# frm-mw-diode-detector.net
KiCad netlist of a schematic drawn in Altium Designer
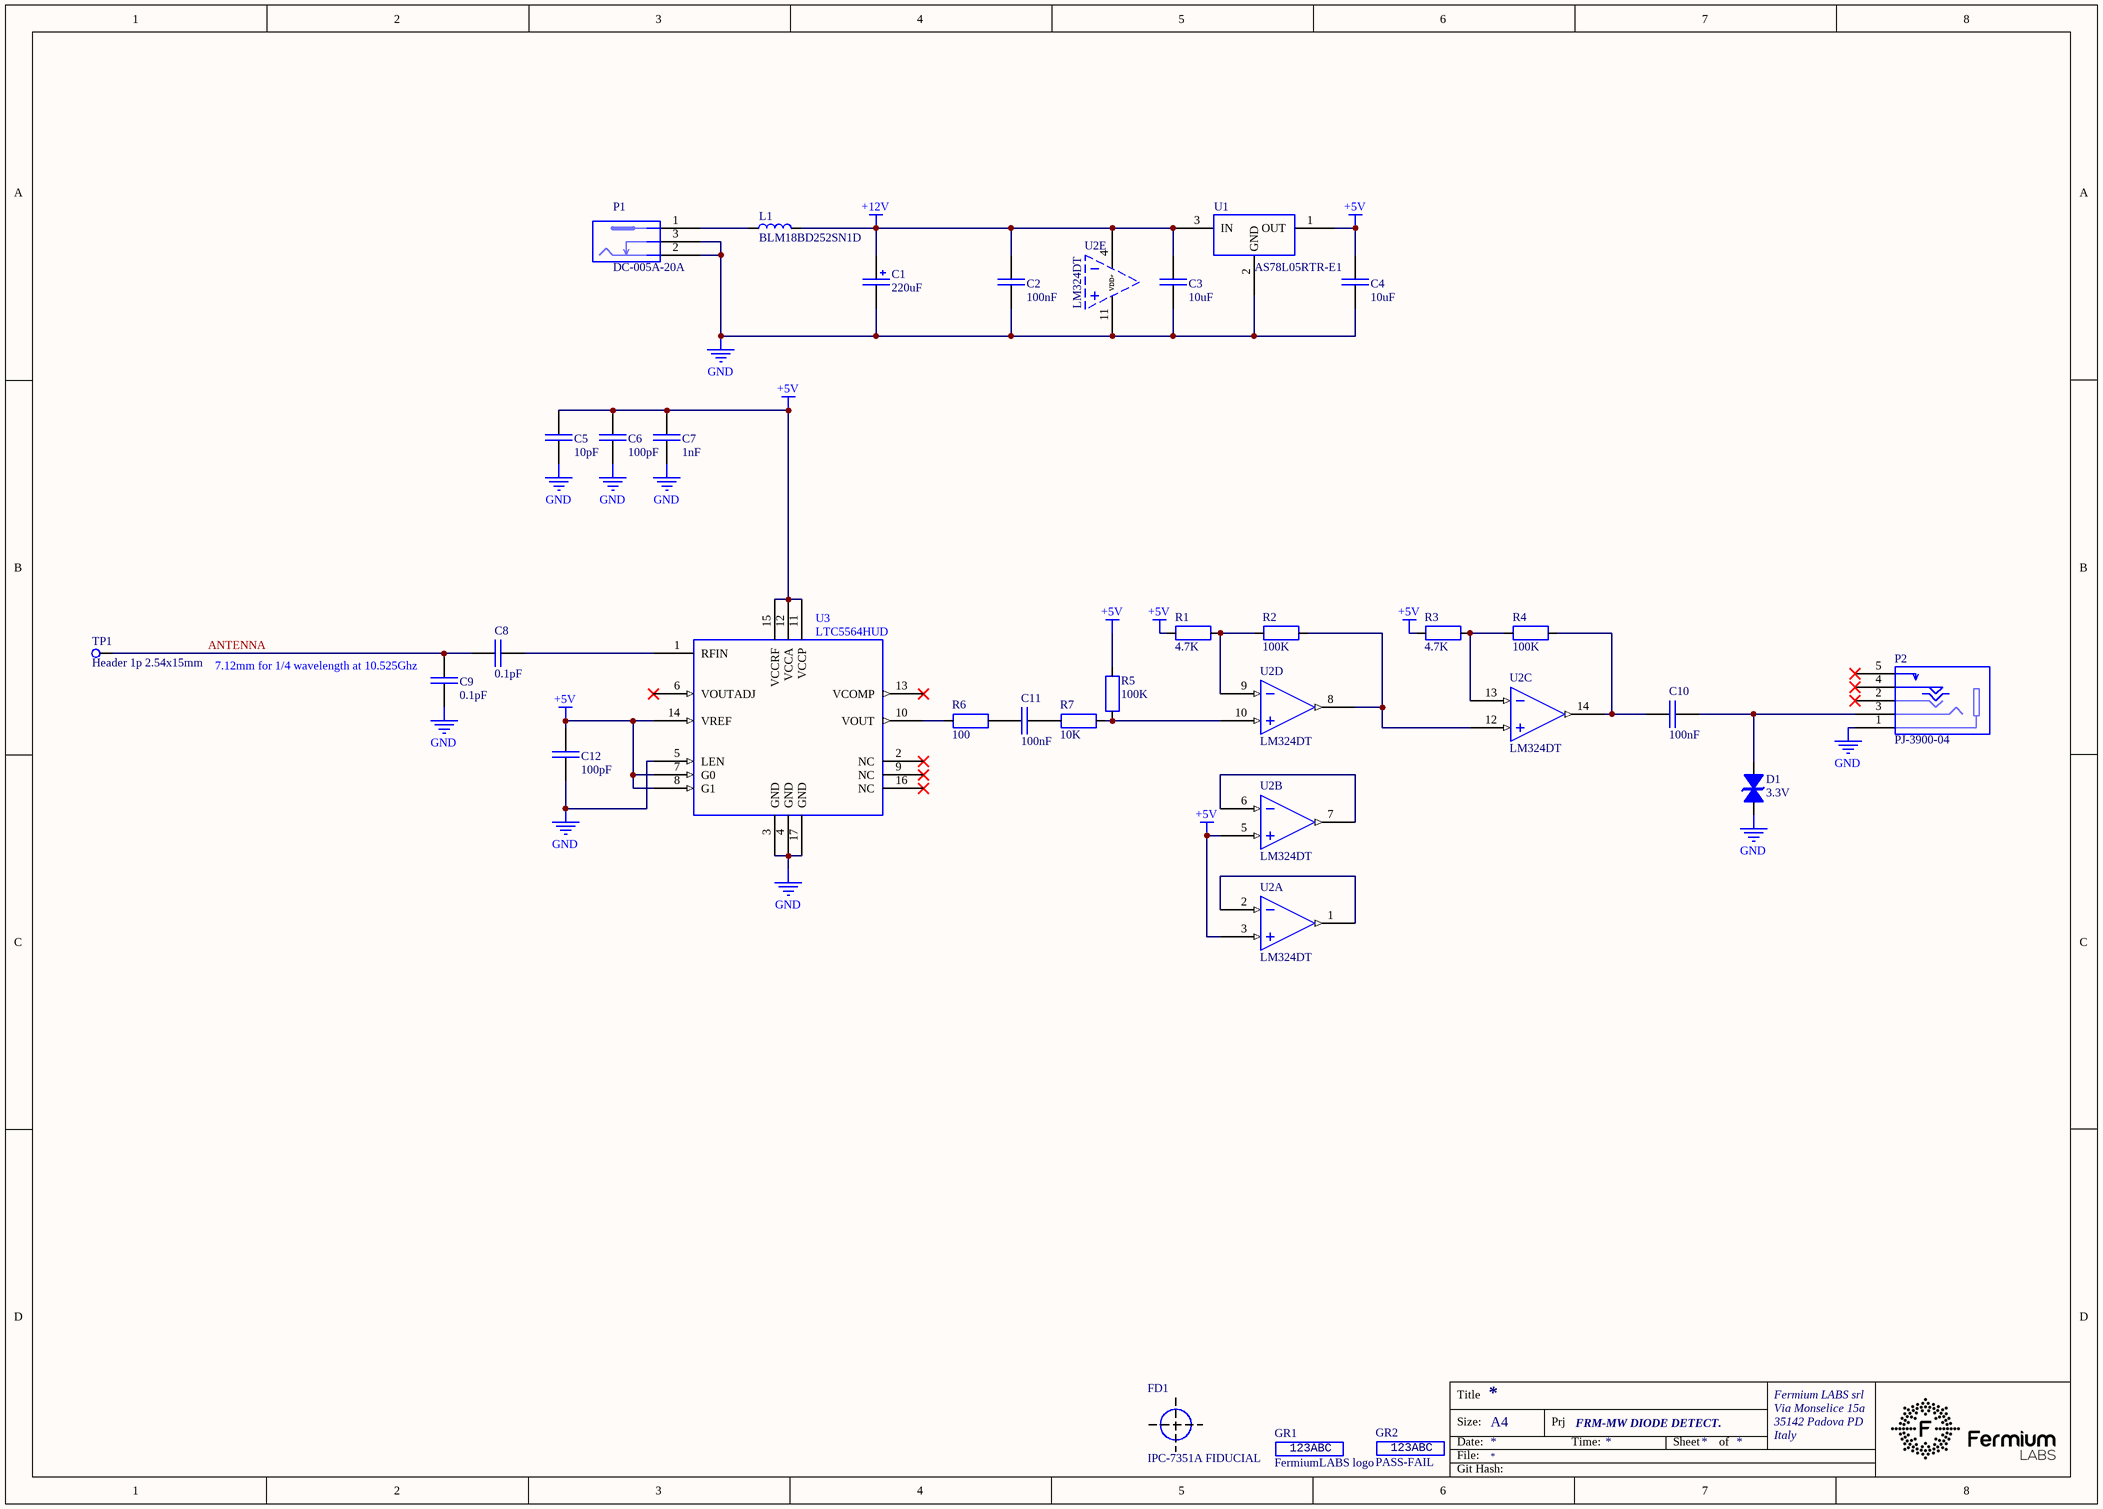
[diagram p0: frm-mw-diode-detector.SchDoc]

(export (version "E")
  (design (tool "Eeschema 10.0.6"))
  (components
    (comp (ref "C1")
      (value "220uF")
      (footprint "3924B366-8672-45E9-B0BE-62DACC24E783")
      (description "CAP  THT ELEC 220uF 25V 20%")
      (fields (field (name "PART NUMBER") "1a28df19-6d3e-4a71-836c-f22920f8e8ab"))
      (libsource (lib "frmdblib") (part "GENERIC_C_ELEC"))
    )
    (comp (ref "C2")
      (value "100nF")
      (footprint "CAP 0603_1608")
      (description "CAP SMD MLCC 100nF 25V 0603 X7R")
      (fields (field (name "PART NUMBER") "02841f84-ac15-41b5-9e17-915f8f067828"))
      (libsource (lib "frmdblib") (part "GENERIC_C"))
    )
    (comp (ref "C3")
      (value "10uF")
      (footprint "CAP 0805_2012")
      (description "CAP SMD MLCC 10uF 25V 0805 X5R")
      (fields (field (name "PART NUMBER") "1ffbe5a9-0884-4740-bdad-20a6a98400e6"))
      (libsource (lib "frmdblib") (part "GENERIC_C"))
    )
    (comp (ref "C4")
      (value "10uF")
      (footprint "CAP 0805_2012")
      (description "CAP SMD MLCC 10uF 25V 0805 X5R")
      (fields (field (name "PART NUMBER") "1ffbe5a9-0884-4740-bdad-20a6a98400e6"))
      (libsource (lib "frmdblib") (part "GENERIC_C"))
    )
    (comp (ref "C5")
      (value "10pF")
      (footprint "CAP 0603_1608")
      (description "CAP SMD MLCC 10pF 50V 0603 C0G/NP0")
      (fields (field (name "PART NUMBER") "b659b677-71ac-4e84-9ac8-47a475f18d31"))
      (libsource (lib "frmdblib") (part "GENERIC_C"))
    )
    (comp (ref "C6")
      (value "100pF")
      (footprint "CAP 0603_1608")
      (description "CAP SMD MLCC 100pF 100V 0603 C0G/NP0")
      (fields (field (name "PART NUMBER") "ccf679fd-1b09-4431-be81-04c3ce295510"))
      (libsource (lib "frmdblib") (part "GENERIC_C"))
    )
    (comp (ref "C7")
      (value "1nF")
      (footprint "CAP 0603_1608")
      (description "CAP SMD MLCC 1nF 50V 0603 X7R")
      (fields (field (name "PART NUMBER") "0eca2548-3630-4fea-a3d5-94248c1cae74"))
      (libsource (lib "frmdblib") (part "GENERIC_C"))
    )
    (comp (ref "C8")
      (value "0.1pF")
      (footprint "CAP 0402_1005 RF")
      (description "CAP SMD MLCC 0.1pF 50V 0402 HIGH-Q")
      (fields (field (name "PART NUMBER") "26a1b8a5-3146-4e38-b8a1-20cf4d8b229c"))
      (libsource (lib "frmdblib") (part "GENERIC_C"))
    )
    (comp (ref "C9")
      (value "0.1pF")
      (footprint "CAP 0402_1005 RF")
      (description "CAP SMD MLCC 0.1pF 50V 0402 HIGH-Q")
      (fields (field (name "PART NUMBER") "26a1b8a5-3146-4e38-b8a1-20cf4d8b229c"))
      (libsource (lib "frmdblib") (part "GENERIC_C"))
    )
    (comp (ref "C10")
      (value "100nF")
      (footprint "CAP 0603_1608")
      (description "CAP SMD MLCC 100nF 25V 0603 X7R")
      (fields (field (name "PART NUMBER") "02841f84-ac15-41b5-9e17-915f8f067828"))
      (libsource (lib "frmdblib") (part "GENERIC_C"))
    )
    (comp (ref "C11")
      (value "100nF")
      (footprint "CAP 0603_1608")
      (description "CAP SMD MLCC 100nF 25V 0603 X7R")
      (fields (field (name "PART NUMBER") "02841f84-ac15-41b5-9e17-915f8f067828"))
      (libsource (lib "frmdblib") (part "GENERIC_C"))
    )
    (comp (ref "C12")
      (value "100pF")
      (footprint "CAP 0603_1608")
      (description "CAP SMD MLCC 100pF 100V 0603 C0G/NP0")
      (fields (field (name "PART NUMBER") "ccf679fd-1b09-4431-be81-04c3ce295510"))
      (libsource (lib "frmdblib") (part "GENERIC_C"))
    )
    (comp (ref "D1")
      (value "3.3V")
      (footprint "SOD523F")
      (description "DIODE SMD TVS 3.3V BIDIRECTIONAL SOD-523")
      (fields (field (name "PART NUMBER") "d6266fd0-7428-4fb9-a062-338cdce926fd"))
      (libsource (lib "frmdblib") (part "GENERIC_D_TVS_BI"))
    )
    (comp (ref "FD1")
      (value "IPC-7351A FIDUCIAL")
      (footprint "FIDUCIAL-IPC-7351A")
      (description "GRAPHICS FIDUCIAL IPC-7351A")
      (fields (field (name "PART NUMBER") "19da4612-eb95-43bb-9984-553a52b2a224"))
      (libsource (lib "frmdblib") (part "GENERIC_FIDUCIAL"))
    )
    (comp (ref "GR1")
      (value "FermiumLABS logo")
      (footprint "5394DE47-A0E8-4329-8464-7791B7C19310")
      (description "GRAPHICS LOGO FERMIUM LABS SRL")
      (fields (field (name "PART NUMBER") "50f8ea88-0034-49fe-a263-d8e97bc35e2f"))
      (libsource (lib "frmdblib") (part "GENERIC_GRAPHIC"))
    )
    (comp (ref "GR2")
      (value "PASS-FAIL")
      (footprint "0B1556B7-A534-4801-B57D-01EFA34B1205")
      (description "GRAPHICS PASS-FAIL MARK")
      (fields (field (name "PART NUMBER") "d1abe19f-3fed-4f20-b2ed-afc0ffbc6628"))
      (libsource (lib "frmdblib") (part "GENERIC_GRAPHIC"))
    )
    (comp (ref "L1")
      (value "BLM18BD252SN1D")
      (footprint "FER 0603_1608")
      (description "FER SMD CHIP 0603 400mA 1k@100MHz 500mOhm")
      (fields (field (name "PART NUMBER") "c9e30ae8-9d5b-4135-a079-b1147da846d8"))
      (libsource (lib "frmdblib") (part "GENERIC_L"))
    )
    (comp (ref "P1")
      (value "DC-005A-20A")
      (footprint "F0972D8A-C5C0-4A84-836D-A9666EE65C2D")
      (description "CONN THT DC JACK 0.5A 30VDC 5Kcycles")
      (fields (field (name "PART NUMBER") "b53db51a-1725-412b-9039-fa7a45c7c438"))
      (libsource (lib "frmdblib") (part "34A1CD0B-E262-46EF-B9F1-39CB809C308F"))
    )
    (comp (ref "P2")
      (value "PJ-3900-04")
      (footprint "7EF2B92C-0FC9-4C85-B662-5CEC65BFCCC4")
      (description "CONN THT 3.5mm AUDIO STEREO AUX SWITCH")
      (fields (field (name "PART NUMBER") "80507a24-5d7c-4cf5-953e-f54832d54564"))
      (libsource (lib "frmdblib") (part "46E41D2F-79BD-46AC-B778-70B2D50A946A"))
    )
    (comp (ref "R1")
      (value "4.7K")
      (description "RES SMD 4.7K OHM 1% 1/10W 0603")
      (fields (field (name "PART NUMBER") "86e7c7d8-c04a-4e9a-bdc1-b1b3729c93a3"))
      (libsource (lib "frmdblib") (part "GENERIC_R"))
    )
    (comp (ref "R2")
      (value "100K")
      (footprint "RES 0603_1608")
      (description "RES SMD 100K OHM 1% 1/10W 0603")
      (fields (field (name "PART NUMBER") "76af10b3-9d85-4b5c-a2d6-26cc74f432f7"))
      (libsource (lib "frmdblib") (part "GENERIC_R"))
    )
    (comp (ref "R3")
      (value "4.7K")
      (description "RES SMD 4.7K OHM 1% 1/10W 0603")
      (fields (field (name "PART NUMBER") "86e7c7d8-c04a-4e9a-bdc1-b1b3729c93a3"))
      (libsource (lib "frmdblib") (part "GENERIC_R"))
    )
    (comp (ref "R4")
      (value "100K")
      (footprint "RES 0603_1608")
      (description "RES SMD 100K OHM 1% 1/10W 0603")
      (fields (field (name "PART NUMBER") "76af10b3-9d85-4b5c-a2d6-26cc74f432f7"))
      (libsource (lib "frmdblib") (part "GENERIC_R"))
    )
    (comp (ref "R5")
      (value "100K")
      (footprint "RES 0603_1608")
      (description "RES SMD 100K OHM 1% 1/10W 0603")
      (fields (field (name "PART NUMBER") "76af10b3-9d85-4b5c-a2d6-26cc74f432f7"))
      (libsource (lib "frmdblib") (part "GENERIC_R"))
    )
    (comp (ref "R6")
      (value "100")
      (description "RES SMD 100 OHM 1% 1/10W 0603")
      (fields (field (name "PART NUMBER") "0a6c4b74-f837-4563-b154-6e196d753525"))
      (libsource (lib "frmdblib") (part "GENERIC_R"))
    )
    (comp (ref "R7")
      (value "10K")
      (footprint "RES 0603_1608")
      (description "RES SMD 10K OHM 1% 1/10W 0603")
      (fields (field (name "PART NUMBER") "93242766-ba1d-462d-b58f-ce1dfc4129c8"))
      (libsource (lib "frmdblib") (part "GENERIC_R"))
    )
    (comp (ref "TP1")
      (value "Header 1p 2.54x15mm")
      (footprint "2C1CB748-2B7B-4AED-959C-BA5F218FC650")
      (description "CONN THT PIN HEADER 1P MALE 2.54mm 15mm HEIGHT")
      (fields (field (name "PART NUMBER") "6533a5d9-7dc1-4b74-ad41-7af9be51a6b8"))
      (libsource (lib "frmdblib") (part "GENERIC_TP"))
    )
    (comp (ref "U1")
      (value "AS78L05RTR-E1")
      (footprint "E733EFB9-FE91-4AE9-9197-29251971C3DC")
      (description "IC SMD LINEAR VOLTAGE REGULATOR 5V 100mA SOT-89")
      (fields (field (name "PART NUMBER") "fd64863e-487f-4688-b264-696c0ba5456b"))
      (libsource (lib "frmdblib") (part "FCB39772-D6AF-4D61-BC58-A46A50428B6B"))
    )
    (comp (ref "U2")
      (value "LM324DT")
      (footprint "34355DA5-B1DA-47C2-A88A-ECF82120A4F7")
      (description "IC SMD OPAMP LM324DT SO-14")
      (fields (field (name "PART NUMBER") "21a85167-c328-42f7-a52e-365842c6dad3"))
      (libsource (lib "frmdblib") (part "B8DB4B19-8E9C-4F46-A390-7A352E041443"))
    )
    (comp (ref "U3")
      (value "LTC5564HUD")
      (footprint "1C9CA8C2-7F7E-4E2B-A488-6DD37E6BADEA")
      (description "IC SMD RF POWER DETECTOR 15GHz LTC5564 QFN-16")
      (fields (field (name "PART NUMBER") "45536c7f-5716-49d5-adce-f87923efcc45"))
      (libsource (lib "frmdblib") (part "E5125104-88FC-432D-8A1A-FA1AA23E8110"))
    )
  )
  (nets
    (net (code "1") (name "+5V") (class "Default")
      (node (ref "C12") (pin "1") (pintype "passive"))
      (node (ref "C4") (pin "2") (pintype "passive"))
      (node (ref "C5") (pin "1") (pintype "passive"))
      (node (ref "C6") (pin "1") (pintype "passive"))
      (node (ref "C7") (pin "1") (pintype "passive"))
      (node (ref "R1") (pin "1") (pintype "passive"))
      (node (ref "R3") (pin "2") (pintype "passive"))
      (node (ref "R5") (pin "2") (pintype "passive"))
      (node (ref "U1") (pin "1") (pinfunction "OUT_1") (pintype "passive"))
      (node (ref "U2") (pin "3") (pinfunction "IN+_3") (pintype "input"))
      (node (ref "U2") (pin "5") (pinfunction "IN+_5") (pintype "input"))
      (node (ref "U3") (pin "11") (pinfunction "VCCP_11") (pintype "power_in"))
      (node (ref "U3") (pin "12") (pinfunction "VCCA_12") (pintype "power_in"))
      (node (ref "U3") (pin "14") (pinfunction "VREF_14") (pintype "input"))
      (node (ref "U3") (pin "15") (pinfunction "VCCRF_15") (pintype "power_in"))
      (node (ref "U3") (pin "7") (pinfunction "G0_7") (pintype "input"))
      (node (ref "U3") (pin "8") (pinfunction "G1_8") (pintype "input"))
    )
    (net (code "2") (name "+12V") (class "Default")
      (node (ref "C1") (pin "1") (pintype "passive"))
      (node (ref "C2") (pin "2") (pintype "passive"))
      (node (ref "C3") (pin "2") (pintype "passive"))
      (node (ref "L1") (pin "2") (pintype "passive"))
      (node (ref "U1") (pin "3") (pinfunction "IN_3") (pintype "passive"))
      (node (ref "U2") (pin "4") (pinfunction "VDD+_4") (pintype "power_in"))
    )
    (net (code "3") (name "/ANTENNA") (class "Default")
      (node (ref "C8") (pin "1") (pintype "passive"))
      (node (ref "C9") (pin "2") (pintype "passive"))
      (node (ref "TP1") (pin "1") (pinfunction "TP_1") (pintype "passive"))
    )
    (net (code "4") (name "GND") (class "Default")
      (node (ref "C1") (pin "2") (pintype "passive"))
      (node (ref "C12") (pin "2") (pintype "passive"))
      (node (ref "C2") (pin "1") (pintype "passive"))
      (node (ref "C3") (pin "1") (pintype "passive"))
      (node (ref "C4") (pin "1") (pintype "passive"))
      (node (ref "C5") (pin "2") (pintype "passive"))
      (node (ref "C6") (pin "2") (pintype "passive"))
      (node (ref "C7") (pin "2") (pintype "passive"))
      (node (ref "C9") (pin "1") (pintype "passive"))
      (node (ref "D1") (pin "2") (pintype "passive"))
      (node (ref "P1") (pin "2") (pinfunction "2_2") (pintype "passive"))
      (node (ref "P1") (pin "3") (pinfunction "3_3") (pintype "passive"))
      (node (ref "P2") (pin "1") (pinfunction "GND_1") (pintype "passive"))
      (node (ref "U1") (pin "2") (pinfunction "GND_2") (pintype "passive"))
      (node (ref "U2") (pin "11") (pinfunction "VDD-_11") (pintype "power_in"))
      (node (ref "U3") (pin "17") (pinfunction "GND_17") (pintype "power_in"))
      (node (ref "U3") (pin "3") (pinfunction "GND_3") (pintype "power_in"))
      (node (ref "U3") (pin "4") (pinfunction "GND_4") (pintype "power_in"))
      (node (ref "U3") (pin "5") (pinfunction "LEN_5") (pintype "input"))
    )
    (net (code "5") (name "Net-(C11-Pad1)") (class "Default")
      (node (ref "C11") (pin "1") (pintype "passive"))
      (node (ref "R6") (pin "2") (pintype "passive"))
    )
    (net (code "6") (name "Net-(C11-Pad2)") (class "Default")
      (node (ref "C11") (pin "2") (pintype "passive"))
      (node (ref "R7") (pin "2") (pintype "passive"))
    )
    (net (code "7") (name "Net-(L1-Pad1)") (class "Default")
      (node (ref "L1") (pin "1") (pintype "passive"))
      (node (ref "P1") (pin "1") (pinfunction "1_1") (pintype "passive"))
    )
    (net (code "8") (name "Net-(P2-L)") (class "Default")
      (node (ref "C10") (pin "2") (pintype "passive"))
      (node (ref "D1") (pin "1") (pintype "passive"))
      (node (ref "P2") (pin "3") (pinfunction "L_3") (pintype "passive"))
    )
    (net (code "9") (name "Net-(U2A-IN-)") (class "Default")
      (node (ref "U2") (pin "1") (pinfunction "OUT_1") (pintype "output"))
      (node (ref "U2") (pin "2") (pinfunction "IN-_2") (pintype "input"))
    )
    (net (code "10") (name "Net-(U2B-IN-)") (class "Default")
      (node (ref "U2") (pin "6") (pinfunction "IN-_6") (pintype "input"))
      (node (ref "U2") (pin "7") (pinfunction "OUT_7") (pintype "output"))
    )
    (net (code "11") (name "Net-(U2C-IN+)") (class "Default")
      (node (ref "R2") (pin "1") (pintype "passive"))
      (node (ref "U2") (pin "12") (pinfunction "IN+_12") (pintype "input"))
      (node (ref "U2") (pin "8") (pinfunction "OUT_8") (pintype "output"))
    )
    (net (code "12") (name "Net-(U2C-IN-)") (class "Default")
      (node (ref "R3") (pin "1") (pintype "passive"))
      (node (ref "R4") (pin "1") (pintype "passive"))
      (node (ref "U2") (pin "13") (pinfunction "IN-_13") (pintype "input"))
    )
    (net (code "13") (name "Net-(U2C-OUT)") (class "Default")
      (node (ref "C10") (pin "1") (pintype "passive"))
      (node (ref "R4") (pin "2") (pintype "passive"))
      (node (ref "U2") (pin "14") (pinfunction "OUT_14") (pintype "output"))
    )
    (net (code "14") (name "Net-(U2D-IN+)") (class "Default")
      (node (ref "R5") (pin "1") (pintype "passive"))
      (node (ref "R7") (pin "1") (pintype "passive"))
      (node (ref "U2") (pin "10") (pinfunction "IN+_10") (pintype "input"))
    )
    (net (code "15") (name "Net-(U2D-IN-)") (class "Default")
      (node (ref "R1") (pin "2") (pintype "passive"))
      (node (ref "R2") (pin "2") (pintype "passive"))
      (node (ref "U2") (pin "9") (pinfunction "IN-_9") (pintype "input"))
    )
    (net (code "16") (name "Net-(U3-RFIN)") (class "Default")
      (node (ref "C8") (pin "2") (pintype "passive"))
      (node (ref "U3") (pin "1") (pinfunction "RFIN_1") (pintype "passive"))
    )
    (net (code "17") (name "Net-(U3-VOUT)") (class "Default")
      (node (ref "R6") (pin "1") (pintype "passive"))
      (node (ref "U3") (pin "10") (pinfunction "VOUT_10") (pintype "output"))
    )
    (net (code "18") (name "unconnected-(P2-AUX-Pad4)") (class "Default")
      (node (ref "P2") (pin "4") (pinfunction "AUX_4") (pintype "passive+no_connect"))
    )
    (net (code "19") (name "unconnected-(P2-AUX-Pad5)") (class "Default")
      (node (ref "P2") (pin "5") (pinfunction "AUX_5") (pintype "passive+no_connect"))
    )
    (net (code "20") (name "unconnected-(P2-R-Pad2)") (class "Default")
      (node (ref "P2") (pin "2") (pinfunction "R_2") (pintype "passive+no_connect"))
    )
    (net (code "21") (name "unconnected-(U3-NC-Pad2)") (class "Default")
      (node (ref "U3") (pin "2") (pinfunction "NC_2") (pintype "passive+no_connect"))
    )
    (net (code "22") (name "unconnected-(U3-NC-Pad9)") (class "Default")
      (node (ref "U3") (pin "9") (pinfunction "NC_9") (pintype "passive+no_connect"))
    )
    (net (code "23") (name "unconnected-(U3-NC-Pad16)") (class "Default")
      (node (ref "U3") (pin "16") (pinfunction "NC_16") (pintype "passive+no_connect"))
    )
    (net (code "24") (name "unconnected-(U3-VCOMP-Pad13)") (class "Default")
      (node (ref "U3") (pin "13") (pinfunction "VCOMP_13") (pintype "output+no_connect"))
    )
    (net (code "25") (name "unconnected-(U3-VOUTADJ-Pad6)") (class "Default")
      (node (ref "U3") (pin "6") (pinfunction "VOUTADJ_6") (pintype "input+no_connect"))
    )
  )
)
